# power_electronics3.net
KiCad netlist of a schematic drawn in EAGLE
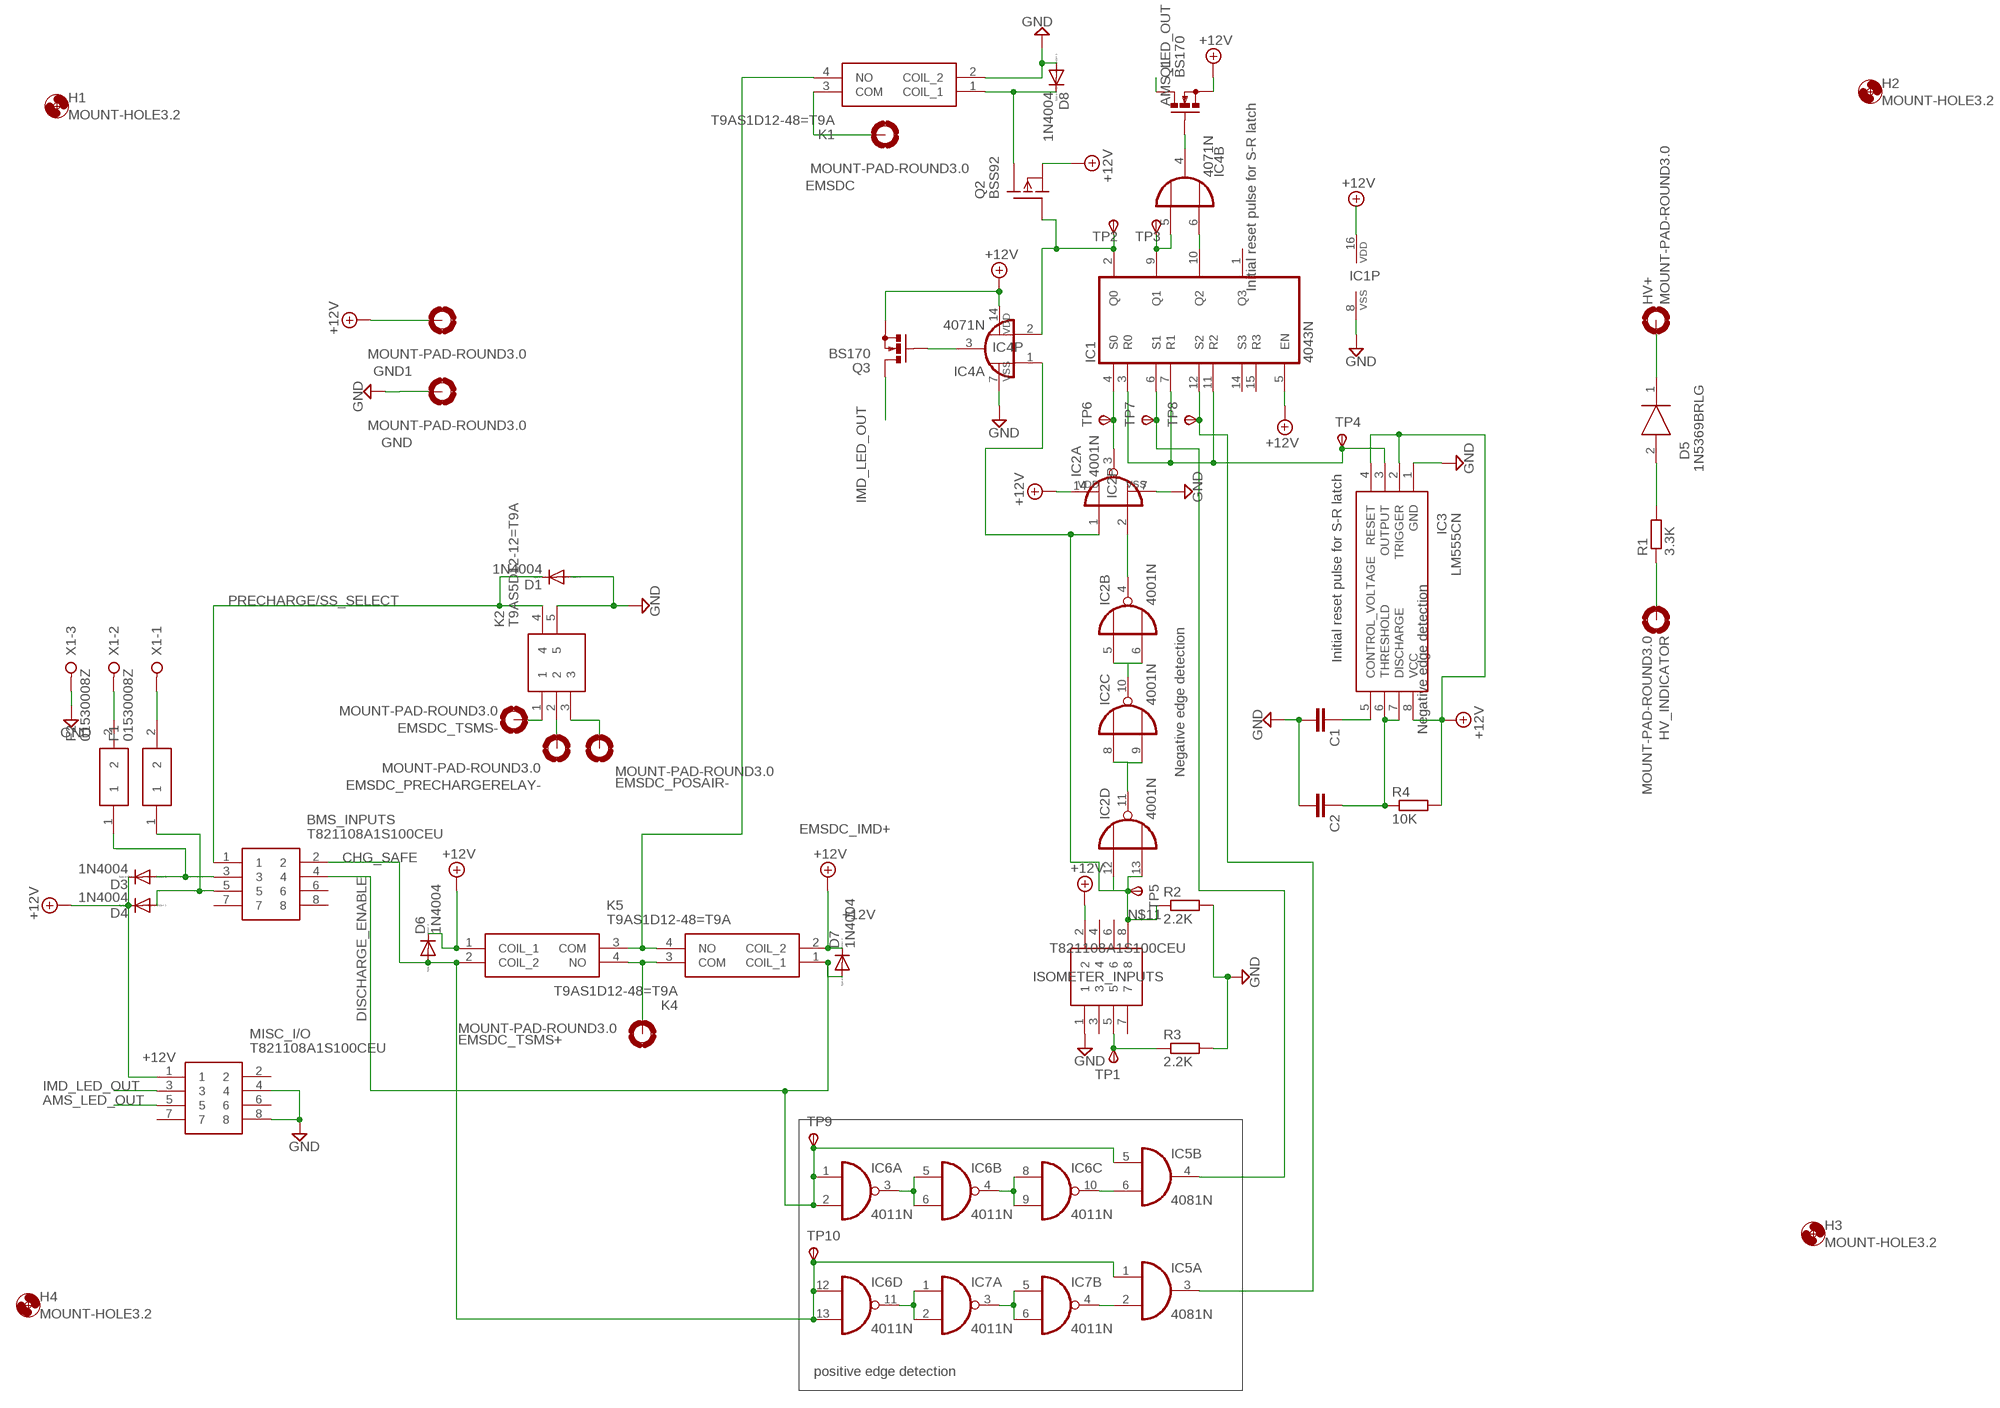
[diagram p0: schematic, sheet 1]

(export (version "E")
  (design (tool "Eeschema 10.0.6"))
  (components
    (comp (ref "BMS_INPUTS")
      (value "T821108A1S100CEU")
      (footprint "eagle-import:HDRV8W64P254_2X4_1778X895X915P")
      (fields (field (name "RS_PART_NUMBER") "8323569"))
      (libsource (lib "eagle-import") (part "T821108A1S100CEU"))
    )
    (comp (ref "C1")
      (value "C-EU050-024X044")
      (footprint "eagle-import:C050-024X044")
      (libsource (lib "eagle-import") (part "C-EU050-024X044"))
    )
    (comp (ref "C2")
      (value "C-EU050-024X044")
      (footprint "eagle-import:C050-024X044")
      (libsource (lib "eagle-import") (part "C-EU050-024X044"))
    )
    (comp (ref "D1")
      (value "1N4004")
      (footprint "eagle-import:DO41-10")
      (libsource (lib "eagle-import") (part "1N4004"))
    )
    (comp (ref "D3")
      (value "1N4004")
      (footprint "eagle-import:DO41-10")
      (libsource (lib "eagle-import") (part "1N4004"))
    )
    (comp (ref "D4")
      (value "1N4004")
      (footprint "eagle-import:DO41-10")
      (libsource (lib "eagle-import") (part "1N4004"))
    )
    (comp (ref "D5")
      (value "1N5369BRLG")
      (footprint "eagle-import:DIOAD2260W109L864D349")
      (fields (field (name "RS_PART_NUMBER") "6547678P"))
      (libsource (lib "eagle-import") (part "1N5369BRLG"))
    )
    (comp (ref "D6")
      (value "1N4004")
      (footprint "eagle-import:DO41-10")
      (libsource (lib "eagle-import") (part "1N4004"))
    )
    (comp (ref "D7")
      (value "1N4004")
      (footprint "eagle-import:DO41-10")
      (libsource (lib "eagle-import") (part "1N4004"))
    )
    (comp (ref "D8")
      (value "1N4004")
      (footprint "eagle-import:DO41-10")
      (libsource (lib "eagle-import") (part "1N4004"))
    )
    (comp (ref "EMSDC")
      (value "MOUNT-PAD-ROUND3.0")
      (footprint "eagle-import:3,0-PAD")
      (libsource (lib "eagle-import") (part "MOUNT-PAD-ROUND3.0"))
    )
    (comp (ref "EMSDC_POSAIR-")
      (value "MOUNT-PAD-ROUND3.0")
      (footprint "eagle-import:3,0-PAD")
      (libsource (lib "eagle-import") (part "MOUNT-PAD-ROUND3.0"))
    )
    (comp (ref "EMSDC_PRECHARGERELAY-")
      (value "MOUNT-PAD-ROUND3.0")
      (footprint "eagle-import:3,0-PAD")
      (libsource (lib "eagle-import") (part "MOUNT-PAD-ROUND3.0"))
    )
    (comp (ref "EMSDC_TSMS+")
      (value "MOUNT-PAD-ROUND3.0")
      (footprint "eagle-import:3,0-PAD")
      (libsource (lib "eagle-import") (part "MOUNT-PAD-ROUND3.0"))
    )
    (comp (ref "EMSDC_TSMS-")
      (value "MOUNT-PAD-ROUND3.0")
      (footprint "eagle-import:3,0-PAD")
      (libsource (lib "eagle-import") (part "MOUNT-PAD-ROUND3.0"))
    )
    (comp (ref "F1")
      (value "01530008Z")
      (footprint "eagle-import:01530008")
      (fields (field (name "RS_PART_NUMBER") "3607317"))
      (libsource (lib "eagle-import") (part "01530008Z"))
    )
    (comp (ref "F2")
      (value "01530008Z")
      (footprint "eagle-import:01530008")
      (fields (field (name "RS_PART_NUMBER") "3607317"))
      (libsource (lib "eagle-import") (part "01530008Z"))
    )
    (comp (ref "GND")
      (value "MOUNT-PAD-ROUND3.0")
      (footprint "eagle-import:3,0-PAD")
      (libsource (lib "eagle-import") (part "MOUNT-PAD-ROUND3.0"))
    )
    (comp (ref "GND1")
      (value "MOUNT-PAD-ROUND3.0")
      (footprint "eagle-import:3,0-PAD")
      (libsource (lib "eagle-import") (part "MOUNT-PAD-ROUND3.0"))
    )
    (comp (ref "H1")
      (value "MOUNT-HOLE3.2")
      (footprint "eagle-import:3,2")
      (libsource (lib "eagle-import") (part "MOUNT-HOLE3.2"))
    )
    (comp (ref "H2")
      (value "MOUNT-HOLE3.2")
      (footprint "eagle-import:3,2")
      (libsource (lib "eagle-import") (part "MOUNT-HOLE3.2"))
    )
    (comp (ref "H3")
      (value "MOUNT-HOLE3.2")
      (footprint "eagle-import:3,2")
      (libsource (lib "eagle-import") (part "MOUNT-HOLE3.2"))
    )
    (comp (ref "H4")
      (value "MOUNT-HOLE3.2")
      (footprint "eagle-import:3,2")
      (libsource (lib "eagle-import") (part "MOUNT-HOLE3.2"))
    )
    (comp (ref "HV+")
      (value "MOUNT-PAD-ROUND3.0")
      (footprint "eagle-import:3,0-PAD")
      (libsource (lib "eagle-import") (part "MOUNT-PAD-ROUND3.0"))
    )
    (comp (ref "HV_INDICATOR")
      (value "MOUNT-PAD-ROUND3.0")
      (footprint "eagle-import:3,0-PAD")
      (libsource (lib "eagle-import") (part "MOUNT-PAD-ROUND3.0"))
    )
    (comp (ref "IC1")
      (value "4043N")
      (footprint "eagle-import:DIL16")
      (libsource (lib "eagle-import") (part "4043N"))
    )
    (comp (ref "IC2")
      (value "4001N")
      (footprint "eagle-import:DIL14")
      (libsource (lib "eagle-import") (part "4001N"))
    )
    (comp (ref "IC3")
      (value "LM555CN")
      (footprint "eagle-import:DIP762W53P254L980H533Q8N")
      (fields (field (name "MOUSER_PART_NUMBER") "512-LM555CN"))
      (libsource (lib "eagle-import") (part "LM555CN"))
    )
    (comp (ref "IC4")
      (value "4071N")
      (footprint "eagle-import:DIL14")
      (libsource (lib "eagle-import") (part "4071N"))
    )
    (comp (ref "IC5")
      (value "4081N")
      (footprint "eagle-import:DIL14")
      (libsource (lib "eagle-import") (part "4081N"))
    )
    (comp (ref "IC6")
      (value "4011N")
      (footprint "eagle-import:DIL14")
      (libsource (lib "eagle-import") (part "4011N"))
    )
    (comp (ref "IC7")
      (value "4011N")
      (footprint "eagle-import:DIL14")
      (libsource (lib "eagle-import") (part "4011N"))
    )
    (comp (ref "ISOMETER_INPUTS")
      (value "T821108A1S100CEU")
      (footprint "eagle-import:HDRV8W64P254_2X4_1778X895X915P")
      (fields (field (name "RS_PART_NUMBER") "8323569"))
      (libsource (lib "eagle-import") (part "T821108A1S100CEU"))
    )
    (comp (ref "K1")
      (value "T9AS1D12-48=T9A")
      (footprint "eagle-import:T9AS1D1248T9A")
      (fields (field (name "RS_PART_NUMBER") "6802534P"))
      (libsource (lib "eagle-import") (part "T9AS1D12-48=T9A"))
    )
    (comp (ref "K2")
      (value "T9AS5D12-12=T9A")
      (footprint "eagle-import:T9AS1D12")
      (fields (field (name "RS_PART_NUMBER") "6802528"))
      (libsource (lib "eagle-import") (part "T9AS5D12-12=T9A"))
    )
    (comp (ref "K4")
      (value "T9AS1D12-48=T9A")
      (footprint "eagle-import:T9AS1D1248T9A")
      (fields (field (name "RS_PART_NUMBER") "6802534P"))
      (libsource (lib "eagle-import") (part "T9AS1D12-48=T9A"))
    )
    (comp (ref "K5")
      (value "T9AS1D12-48=T9A")
      (footprint "eagle-import:T9AS1D1248T9A")
      (fields (field (name "RS_PART_NUMBER") "6802534P"))
      (libsource (lib "eagle-import") (part "T9AS1D12-48=T9A"))
    )
    (comp (ref "MISC_I/O")
      (value "T821108A1S100CEU")
      (footprint "eagle-import:HDRV8W64P254_2X4_1778X895X915P")
      (fields (field (name "RS_PART_NUMBER") "8323569"))
      (libsource (lib "eagle-import") (part "T821108A1S100CEU"))
    )
    (comp (ref "Q1")
      (value "BS170")
      (footprint "eagle-import:SOT54E")
      (libsource (lib "eagle-import") (part "BS170"))
    )
    (comp (ref "Q2")
      (value "BSS92")
      (footprint "eagle-import:TO92")
      (libsource (lib "eagle-import") (part "BSS92"))
    )
    (comp (ref "Q3")
      (value "BS170")
      (footprint "eagle-import:SOT54E")
      (libsource (lib "eagle-import") (part "BS170"))
    )
    (comp (ref "R1")
      (value "3.3K")
      (footprint "eagle-import:0207_15")
      (libsource (lib "eagle-import") (part "R-EU_0207/15"))
    )
    (comp (ref "R2")
      (value "2.2K")
      (footprint "eagle-import:0207_12")
      (libsource (lib "eagle-import") (part "R-EU_0207/12"))
    )
    (comp (ref "R3")
      (value "2.2K")
      (footprint "eagle-import:0207_12")
      (libsource (lib "eagle-import") (part "R-EU_0207/12"))
    )
    (comp (ref "R4")
      (value "10K")
      (footprint "eagle-import:0207_15")
      (libsource (lib "eagle-import") (part "R-EU_0207/15"))
    )
    (comp (ref "TP1")
      (value "TPSPAD1-17")
      (footprint "eagle-import:P1-17")
      (libsource (lib "eagle-import") (part "TPSPAD1-17"))
    )
    (comp (ref "TP2")
      (value "TPSPAD1-17")
      (footprint "eagle-import:P1-17")
      (libsource (lib "eagle-import") (part "TPSPAD1-17"))
    )
    (comp (ref "TP3")
      (value "TPSPAD1-17")
      (footprint "eagle-import:P1-17")
      (libsource (lib "eagle-import") (part "TPSPAD1-17"))
    )
    (comp (ref "TP4")
      (value "TPSPAD1-17")
      (footprint "eagle-import:P1-17")
      (libsource (lib "eagle-import") (part "TPSPAD1-17"))
    )
    (comp (ref "TP5")
      (value "TPSPAD1-17")
      (footprint "eagle-import:P1-17")
      (libsource (lib "eagle-import") (part "TPSPAD1-17"))
    )
    (comp (ref "TP6")
      (value "TPSPAD1-17")
      (footprint "eagle-import:P1-17")
      (libsource (lib "eagle-import") (part "TPSPAD1-17"))
    )
    (comp (ref "TP7")
      (value "TPSPAD1-17")
      (footprint "eagle-import:P1-17")
      (libsource (lib "eagle-import") (part "TPSPAD1-17"))
    )
    (comp (ref "TP8")
      (value "TPSPAD1-17")
      (footprint "eagle-import:P1-17")
      (libsource (lib "eagle-import") (part "TPSPAD1-17"))
    )
    (comp (ref "TP9")
      (value "TPSPAD1-17")
      (footprint "eagle-import:P1-17")
      (libsource (lib "eagle-import") (part "TPSPAD1-17"))
    )
    (comp (ref "TP10")
      (value "TPSPAD1-17")
      (footprint "eagle-import:P1-17")
      (libsource (lib "eagle-import") (part "TPSPAD1-17"))
    )
    (comp (ref "X1")
      (value "W237-3E")
      (footprint "eagle-import:W237-3E")
      (libsource (lib "eagle-import") (part "W237-3E"))
    )
  )
  (nets
    (net (code "1") (name "+12V") (class "Default")
      (node (ref "D3") (pin "C") (pinfunction "C_C") (pintype "passive"))
      (node (ref "D4") (pin "C") (pinfunction "C_C") (pintype "passive"))
      (node (ref "D6") (pin "C") (pinfunction "C_C") (pintype "passive"))
      (node (ref "D7") (pin "C") (pinfunction "C_C") (pintype "passive"))
      (node (ref "GND1") (pin "B3,0") (pinfunction "MOUNT_B3,0") (pintype "passive"))
      (node (ref "IC1") (pin "16") (pinfunction "VDD_16") (pintype "power_in"))
      (node (ref "IC1") (pin "5") (pinfunction "EN_5") (pintype "input"))
      (node (ref "IC2") (pin "14") (pinfunction "VDD_14") (pintype "power_in"))
      (node (ref "IC3") (pin "2") (pinfunction "TRIGGER_2") (pintype "bidirectional"))
      (node (ref "IC3") (pin "4") (pinfunction "RESET_4") (pintype "bidirectional"))
      (node (ref "IC3") (pin "8") (pinfunction "VCC_8") (pintype "bidirectional"))
      (node (ref "IC4") (pin "14") (pinfunction "VDD_14") (pintype "power_in"))
      (node (ref "ISOMETER_INPUTS") (pin "2") (pinfunction "2_2") (pintype "bidirectional"))
      (node (ref "K4") (pin "2") (pinfunction "COIL_2_2") (pintype "bidirectional"))
      (node (ref "K5") (pin "1") (pinfunction "COIL_1_1") (pintype "bidirectional"))
      (node (ref "MISC_I/O") (pin "1") (pinfunction "1_1") (pintype "bidirectional"))
      (node (ref "Q1") (pin "S") (pinfunction "S_S") (pintype "passive"))
      (node (ref "Q2") (pin "3") (pinfunction "S_3") (pintype "passive"))
      (node (ref "Q3") (pin "S") (pinfunction "S_S") (pintype "passive"))
      (node (ref "R4") (pin "2") (pinfunction "2_2") (pintype "passive"))
    )
    (net (code "2") (name "/AMS_LED_OUT") (class "Default")
      (node (ref "MISC_I/O") (pin "5") (pinfunction "5_5") (pintype "bidirectional"))
      (node (ref "Q1") (pin "D") (pinfunction "D_D") (pintype "passive"))
    )
    (net (code "3") (name "/CHG_SAFE") (class "Default")
      (node (ref "BMS_INPUTS") (pin "2") (pinfunction "2_2") (pintype "bidirectional"))
      (node (ref "D6") (pin "A") (pinfunction "A_A") (pintype "passive"))
      (node (ref "IC5") (pin "1") (pinfunction "I0_1") (pintype "input"))
      (node (ref "IC6") (pin "12") (pinfunction "I0_12") (pintype "input"))
      (node (ref "IC6") (pin "13") (pinfunction "I1_13") (pintype "input"))
      (node (ref "K5") (pin "2") (pinfunction "COIL_2_2") (pintype "bidirectional"))
      (node (ref "TP10") (pin "TP") (pinfunction "PP_TP") (pintype "input"))
    )
    (net (code "4") (name "/DISCHARGE_ENABLE") (class "Default")
      (node (ref "BMS_INPUTS") (pin "4") (pinfunction "4_4") (pintype "bidirectional"))
      (node (ref "D7") (pin "A") (pinfunction "A_A") (pintype "passive"))
      (node (ref "IC5") (pin "5") (pinfunction "I0_5") (pintype "input"))
      (node (ref "IC6") (pin "1") (pinfunction "I0_1") (pintype "input"))
      (node (ref "IC6") (pin "2") (pinfunction "I1_2") (pintype "input"))
      (node (ref "K4") (pin "1") (pinfunction "COIL_1_1") (pintype "bidirectional"))
      (node (ref "TP9") (pin "TP") (pinfunction "PP_TP") (pintype "input"))
    )
    (net (code "5") (name "/EMSDC_IMD+") (class "Default")
      (node (ref "K1") (pin "4") (pinfunction "NO_4") (pintype "bidirectional"))
      (node (ref "K4") (pin "4") (pinfunction "NO_4") (pintype "bidirectional"))
      (node (ref "K5") (pin "3") (pinfunction "COM_3") (pintype "bidirectional"))
    )
    (net (code "6") (name "/IMD_LED_OUT") (class "Default")
      (node (ref "MISC_I/O") (pin "3") (pinfunction "3_3") (pintype "bidirectional"))
      (node (ref "Q3") (pin "D") (pinfunction "D_D") (pintype "passive"))
    )
    (net (code "7") (name "/N$11") (class "Default")
      (node (ref "IC2") (pin "1") (pinfunction "I0_1") (pintype "input"))
      (node (ref "IC2") (pin "12") (pinfunction "I0_12") (pintype "input"))
      (node (ref "IC2") (pin "13") (pinfunction "I1_13") (pintype "input"))
      (node (ref "IC4") (pin "1") (pinfunction "I0_1") (pintype "input"))
      (node (ref "ISOMETER_INPUTS") (pin "8") (pinfunction "8_8") (pintype "bidirectional"))
      (node (ref "R2") (pin "1") (pinfunction "1_1") (pintype "passive"))
      (node (ref "TP5") (pin "TP") (pinfunction "PP_TP") (pintype "input"))
    )
    (net (code "8") (name "/PRECHARGE{slash}SS_SELECT") (class "Default")
      (node (ref "BMS_INPUTS") (pin "1") (pinfunction "1_1") (pintype "bidirectional"))
      (node (ref "D1") (pin "C") (pinfunction "C_C") (pintype "passive"))
      (node (ref "K2") (pin "4") (pinfunction "4_4") (pintype "bidirectional"))
    )
    (net (code "9") (name "GND") (class "Default")
      (node (ref "C1") (pin "2") (pinfunction "2_2") (pintype "passive"))
      (node (ref "C2") (pin "2") (pinfunction "2_2") (pintype "passive"))
      (node (ref "D1") (pin "A") (pinfunction "A_A") (pintype "passive"))
      (node (ref "D8") (pin "A") (pinfunction "A_A") (pintype "passive"))
      (node (ref "GND") (pin "B3,0") (pinfunction "MOUNT_B3,0") (pintype "passive"))
      (node (ref "IC1") (pin "8") (pinfunction "VSS_8") (pintype "power_in"))
      (node (ref "IC2") (pin "7") (pinfunction "VSS_7") (pintype "power_in"))
      (node (ref "IC3") (pin "1") (pinfunction "GND_1") (pintype "bidirectional"))
      (node (ref "IC4") (pin "7") (pinfunction "VSS_7") (pintype "power_in"))
      (node (ref "ISOMETER_INPUTS") (pin "1") (pinfunction "1_1") (pintype "bidirectional"))
      (node (ref "K1") (pin "2") (pinfunction "COIL_2_2") (pintype "bidirectional"))
      (node (ref "K2") (pin "5") (pinfunction "5_5") (pintype "bidirectional"))
      (node (ref "MISC_I/O") (pin "4") (pinfunction "4_4") (pintype "bidirectional"))
      (node (ref "MISC_I/O") (pin "8") (pinfunction "8_8") (pintype "bidirectional"))
      (node (ref "R2") (pin "2") (pinfunction "2_2") (pintype "passive"))
      (node (ref "R3") (pin "2") (pinfunction "2_2") (pintype "passive"))
      (node (ref "X1") (pin "3") (pinfunction "KL_3") (pintype "passive"))
    )
    (net (code "10") (name "Net-(BMS_INPUTS-Pad3)") (class "Default")
      (node (ref "BMS_INPUTS") (pin "3") (pinfunction "3_3") (pintype "bidirectional"))
      (node (ref "D3") (pin "A") (pinfunction "A_A") (pintype "passive"))
      (node (ref "F2") (pin "1") (pinfunction "1_1") (pintype "bidirectional"))
    )
    (net (code "11") (name "Net-(BMS_INPUTS-Pad5)") (class "Default")
      (node (ref "BMS_INPUTS") (pin "5") (pinfunction "5_5") (pintype "bidirectional"))
      (node (ref "D4") (pin "A") (pinfunction "A_A") (pintype "passive"))
      (node (ref "F1") (pin "1") (pinfunction "1_1") (pintype "bidirectional"))
    )
    (net (code "12") (name "Net-(D5-A)") (class "Default")
      (node (ref "D5") (pin "2") (pinfunction "A_2") (pintype "bidirectional"))
      (node (ref "R1") (pin "2") (pinfunction "2_2") (pintype "passive"))
    )
    (net (code "13") (name "Net-(D5-K)") (class "Default")
      (node (ref "D5") (pin "1") (pinfunction "K_1") (pintype "bidirectional"))
      (node (ref "HV+") (pin "B3,0") (pinfunction "MOUNT_B3,0") (pintype "passive"))
    )
    (net (code "14") (name "Net-(EMSDC-MOUNT)") (class "Default")
      (node (ref "EMSDC") (pin "B3,0") (pinfunction "MOUNT_B3,0") (pintype "passive"))
      (node (ref "K1") (pin "3") (pinfunction "COM_3") (pintype "bidirectional"))
    )
    (net (code "15") (name "Net-(EMSDC_POSAIR--MOUNT)") (class "Default")
      (node (ref "EMSDC_POSAIR-") (pin "B3,0") (pinfunction "MOUNT_B3,0") (pintype "passive"))
      (node (ref "K2") (pin "3") (pinfunction "3_3") (pintype "bidirectional"))
    )
    (net (code "16") (name "Net-(EMSDC_PRECHARGERELAY--MOUNT)") (class "Default")
      (node (ref "EMSDC_PRECHARGERELAY-") (pin "B3,0") (pinfunction "MOUNT_B3,0") (pintype "passive"))
      (node (ref "K2") (pin "2") (pinfunction "2_2") (pintype "bidirectional"))
    )
    (net (code "17") (name "Net-(EMSDC_TSMS+-MOUNT)") (class "Default")
      (node (ref "EMSDC_TSMS+") (pin "B3,0") (pinfunction "MOUNT_B3,0") (pintype "passive"))
      (node (ref "K4") (pin "3") (pinfunction "COM_3") (pintype "bidirectional"))
      (node (ref "K5") (pin "4") (pinfunction "NO_4") (pintype "bidirectional"))
    )
    (net (code "18") (name "Net-(EMSDC_TSMS--MOUNT)") (class "Default")
      (node (ref "EMSDC_TSMS-") (pin "B3,0") (pinfunction "MOUNT_B3,0") (pintype "passive"))
      (node (ref "K2") (pin "1") (pinfunction "1_1") (pintype "bidirectional"))
    )
    (net (code "19") (name "Net-(HV_INDICATOR-MOUNT)") (class "Default")
      (node (ref "HV_INDICATOR") (pin "B3,0") (pinfunction "MOUNT_B3,0") (pintype "passive"))
      (node (ref "R1") (pin "1") (pinfunction "1_1") (pintype "passive"))
    )
    (net (code "20") (name "Net-(IC1A-Q0)") (class "Default")
      (node (ref "IC1") (pin "2") (pinfunction "Q0_2") (pintype "output"))
      (node (ref "IC4") (pin "2") (pinfunction "I1_2") (pintype "input"))
      (node (ref "Q2") (pin "1") (pinfunction "G_1") (pintype "passive"))
      (node (ref "TP2") (pin "TP") (pinfunction "PP_TP") (pintype "input"))
    )
    (net (code "21") (name "Net-(IC1A-Q1)") (class "Default")
      (node (ref "IC1") (pin "9") (pinfunction "Q1_9") (pintype "output"))
      (node (ref "IC4") (pin "5") (pinfunction "I0_5") (pintype "input"))
      (node (ref "TP3") (pin "TP") (pinfunction "PP_TP") (pintype "input"))
    )
    (net (code "22") (name "Net-(IC1A-Q2)") (class "Default")
      (node (ref "IC1") (pin "10") (pinfunction "Q2_10") (pintype "output"))
      (node (ref "IC4") (pin "6") (pinfunction "I1_6") (pintype "input"))
    )
    (net (code "23") (name "Net-(IC1A-R0)") (class "Default")
      (node (ref "IC1") (pin "11") (pinfunction "R2_11") (pintype "input"))
      (node (ref "IC1") (pin "3") (pinfunction "R0_3") (pintype "input"))
      (node (ref "IC1") (pin "7") (pinfunction "R1_7") (pintype "input"))
      (node (ref "IC3") (pin "3") (pinfunction "OUTPUT_3") (pintype "bidirectional"))
      (node (ref "TP4") (pin "TP") (pinfunction "PP_TP") (pintype "input"))
    )
    (net (code "24") (name "Net-(IC1A-S0)") (class "Default")
      (node (ref "IC1") (pin "4") (pinfunction "S0_4") (pintype "input"))
      (node (ref "IC2") (pin "3") (pinfunction "O_3") (pintype "output"))
      (node (ref "TP6") (pin "TP") (pinfunction "PP_TP") (pintype "input"))
    )
    (net (code "25") (name "Net-(IC1A-S1)") (class "Default")
      (node (ref "IC1") (pin "6") (pinfunction "S1_6") (pintype "input"))
      (node (ref "IC5") (pin "4") (pinfunction "O_4") (pintype "output"))
      (node (ref "TP7") (pin "TP") (pinfunction "PP_TP") (pintype "input"))
    )
    (net (code "26") (name "Net-(IC1A-S2)") (class "Default")
      (node (ref "IC1") (pin "12") (pinfunction "S2_12") (pintype "input"))
      (node (ref "IC5") (pin "3") (pinfunction "O_3") (pintype "output"))
      (node (ref "TP8") (pin "TP") (pinfunction "PP_TP") (pintype "input"))
    )
    (net (code "27") (name "Net-(IC2A-I1)") (class "Default")
      (node (ref "IC2") (pin "2") (pinfunction "I1_2") (pintype "input"))
      (node (ref "IC2") (pin "4") (pinfunction "O_4") (pintype "output"))
    )
    (net (code "28") (name "Net-(IC2B-I0)") (class "Default")
      (node (ref "IC2") (pin "10") (pinfunction "O_10") (pintype "output"))
      (node (ref "IC2") (pin "5") (pinfunction "I0_5") (pintype "input"))
      (node (ref "IC2") (pin "6") (pinfunction "I1_6") (pintype "input"))
    )
    (net (code "29") (name "Net-(IC2C-I0)") (class "Default")
      (node (ref "IC2") (pin "11") (pinfunction "O_11") (pintype "output"))
      (node (ref "IC2") (pin "8") (pinfunction "I0_8") (pintype "input"))
      (node (ref "IC2") (pin "9") (pinfunction "I1_9") (pintype "input"))
    )
    (net (code "30") (name "Net-(IC3-CONTROL_VOLTAGE)") (class "Default")
      (node (ref "C1") (pin "1") (pinfunction "1_1") (pintype "passive"))
      (node (ref "IC3") (pin "5") (pinfunction "CONTROL_VOLTAGE_5") (pintype "bidirectional"))
    )
    (net (code "31") (name "Net-(IC3-DISCHARGE)") (class "Default")
      (node (ref "C2") (pin "1") (pinfunction "1_1") (pintype "passive"))
      (node (ref "IC3") (pin "6") (pinfunction "THRESHOLD_6") (pintype "bidirectional"))
      (node (ref "IC3") (pin "7") (pinfunction "DISCHARGE_7") (pintype "bidirectional"))
      (node (ref "R4") (pin "1") (pinfunction "1_1") (pintype "passive"))
    )
    (net (code "32") (name "Net-(IC4A-O)") (class "Default")
      (node (ref "IC4") (pin "3") (pinfunction "O_3") (pintype "output"))
      (node (ref "Q3") (pin "G") (pinfunction "G_G") (pintype "passive"))
    )
    (net (code "33") (name "Net-(IC4B-O)") (class "Default")
      (node (ref "IC4") (pin "4") (pinfunction "O_4") (pintype "output"))
      (node (ref "Q1") (pin "G") (pinfunction "G_G") (pintype "passive"))
    )
    (net (code "34") (name "Net-(IC5A-I1)") (class "Default")
      (node (ref "IC5") (pin "2") (pinfunction "I1_2") (pintype "input"))
      (node (ref "IC7") (pin "4") (pinfunction "O_4") (pintype "output"))
    )
    (net (code "35") (name "Net-(IC5B-I1)") (class "Default")
      (node (ref "IC5") (pin "6") (pinfunction "I1_6") (pintype "input"))
      (node (ref "IC6") (pin "10") (pinfunction "O_10") (pintype "output"))
    )
    (net (code "36") (name "Net-(IC6A-O)") (class "Default")
      (node (ref "IC6") (pin "3") (pinfunction "O_3") (pintype "output"))
      (node (ref "IC6") (pin "5") (pinfunction "I0_5") (pintype "input"))
      (node (ref "IC6") (pin "6") (pinfunction "I1_6") (pintype "input"))
    )
    (net (code "37") (name "Net-(IC6B-O)") (class "Default")
      (node (ref "IC6") (pin "4") (pinfunction "O_4") (pintype "output"))
      (node (ref "IC6") (pin "8") (pinfunction "I0_8") (pintype "input"))
      (node (ref "IC6") (pin "9") (pinfunction "I1_9") (pintype "input"))
    )
    (net (code "38") (name "Net-(IC6D-O)") (class "Default")
      (node (ref "IC6") (pin "11") (pinfunction "O_11") (pintype "output"))
      (node (ref "IC7") (pin "1") (pinfunction "I0_1") (pintype "input"))
      (node (ref "IC7") (pin "2") (pinfunction "I1_2") (pintype "input"))
    )
    (net (code "39") (name "Net-(IC7A-O)") (class "Default")
      (node (ref "IC7") (pin "3") (pinfunction "O_3") (pintype "output"))
      (node (ref "IC7") (pin "5") (pinfunction "I0_5") (pintype "input"))
      (node (ref "IC7") (pin "6") (pinfunction "I1_6") (pintype "input"))
    )
    (net (code "40") (name "Net-(K1-COIL_1)") (class "Default")
      (node (ref "D8") (pin "C") (pinfunction "C_C") (pintype "passive"))
      (node (ref "K1") (pin "1") (pinfunction "COIL_1_1") (pintype "bidirectional"))
      (node (ref "Q2") (pin "2") (pinfunction "D_2") (pintype "passive"))
    )
    (net (code "41") (name "Net-(TP1-PP)") (class "Default")
      (node (ref "ISOMETER_INPUTS") (pin "5") (pinfunction "5_5") (pintype "bidirectional"))
      (node (ref "R3") (pin "1") (pinfunction "1_1") (pintype "passive"))
      (node (ref "TP1") (pin "TP") (pinfunction "PP_TP") (pintype "input"))
    )
    (net (code "42") (name "Net-(X1A-KL)") (class "Default")
      (node (ref "F1") (pin "2") (pinfunction "2_2") (pintype "bidirectional"))
      (node (ref "X1") (pin "1") (pinfunction "KL_1") (pintype "passive"))
    )
    (net (code "43") (name "Net-(X1B-KL)") (class "Default")
      (node (ref "F2") (pin "2") (pinfunction "2_2") (pintype "bidirectional"))
      (node (ref "X1") (pin "2") (pinfunction "KL_2") (pintype "passive"))
    )
    (net (code "44") (name "unconnected-(BMS_INPUTS-Pad6)") (class "Default")
      (node (ref "BMS_INPUTS") (pin "6") (pinfunction "6_6") (pintype "bidirectional"))
    )
    (net (code "45") (name "unconnected-(BMS_INPUTS-Pad7)") (class "Default")
      (node (ref "BMS_INPUTS") (pin "7") (pinfunction "7_7") (pintype "bidirectional"))
    )
    (net (code "46") (name "unconnected-(BMS_INPUTS-Pad8)") (class "Default")
      (node (ref "BMS_INPUTS") (pin "8") (pinfunction "8_8") (pintype "bidirectional"))
    )
    (net (code "47") (name "unconnected-(IC1A-Q3-Pad1)") (class "Default")
      (node (ref "IC1") (pin "1") (pinfunction "Q3_1") (pintype "output"))
    )
    (net (code "48") (name "unconnected-(IC1A-R3-Pad15)") (class "Default")
      (node (ref "IC1") (pin "15") (pinfunction "R3_15") (pintype "input"))
    )
    (net (code "49") (name "unconnected-(IC1A-S3-Pad14)") (class "Default")
      (node (ref "IC1") (pin "14") (pinfunction "S3_14") (pintype "input"))
    )
    (net (code "50") (name "unconnected-(ISOMETER_INPUTS-Pad3)") (class "Default")
      (node (ref "ISOMETER_INPUTS") (pin "3") (pinfunction "3_3") (pintype "bidirectional"))
    )
    (net (code "51") (name "unconnected-(ISOMETER_INPUTS-Pad4)") (class "Default")
      (node (ref "ISOMETER_INPUTS") (pin "4") (pinfunction "4_4") (pintype "bidirectional"))
    )
    (net (code "52") (name "unconnected-(ISOMETER_INPUTS-Pad6)") (class "Default")
      (node (ref "ISOMETER_INPUTS") (pin "6") (pinfunction "6_6") (pintype "bidirectional"))
    )
    (net (code "53") (name "unconnected-(ISOMETER_INPUTS-Pad7)") (class "Default")
      (node (ref "ISOMETER_INPUTS") (pin "7") (pinfunction "7_7") (pintype "bidirectional"))
    )
    (net (code "54") (name "unconnected-(MISC_I/O-Pad2)") (class "Default")
      (node (ref "MISC_I/O") (pin "2") (pinfunction "2_2") (pintype "bidirectional"))
    )
    (net (code "55") (name "unconnected-(MISC_I/O-Pad6)") (class "Default")
      (node (ref "MISC_I/O") (pin "6") (pinfunction "6_6") (pintype "bidirectional"))
    )
    (net (code "56") (name "unconnected-(MISC_I/O-Pad7)") (class "Default")
      (node (ref "MISC_I/O") (pin "7") (pinfunction "7_7") (pintype "bidirectional"))
    )
  )
)
